# top.net
KiCad netlist of a schematic drawn in Altium Designer
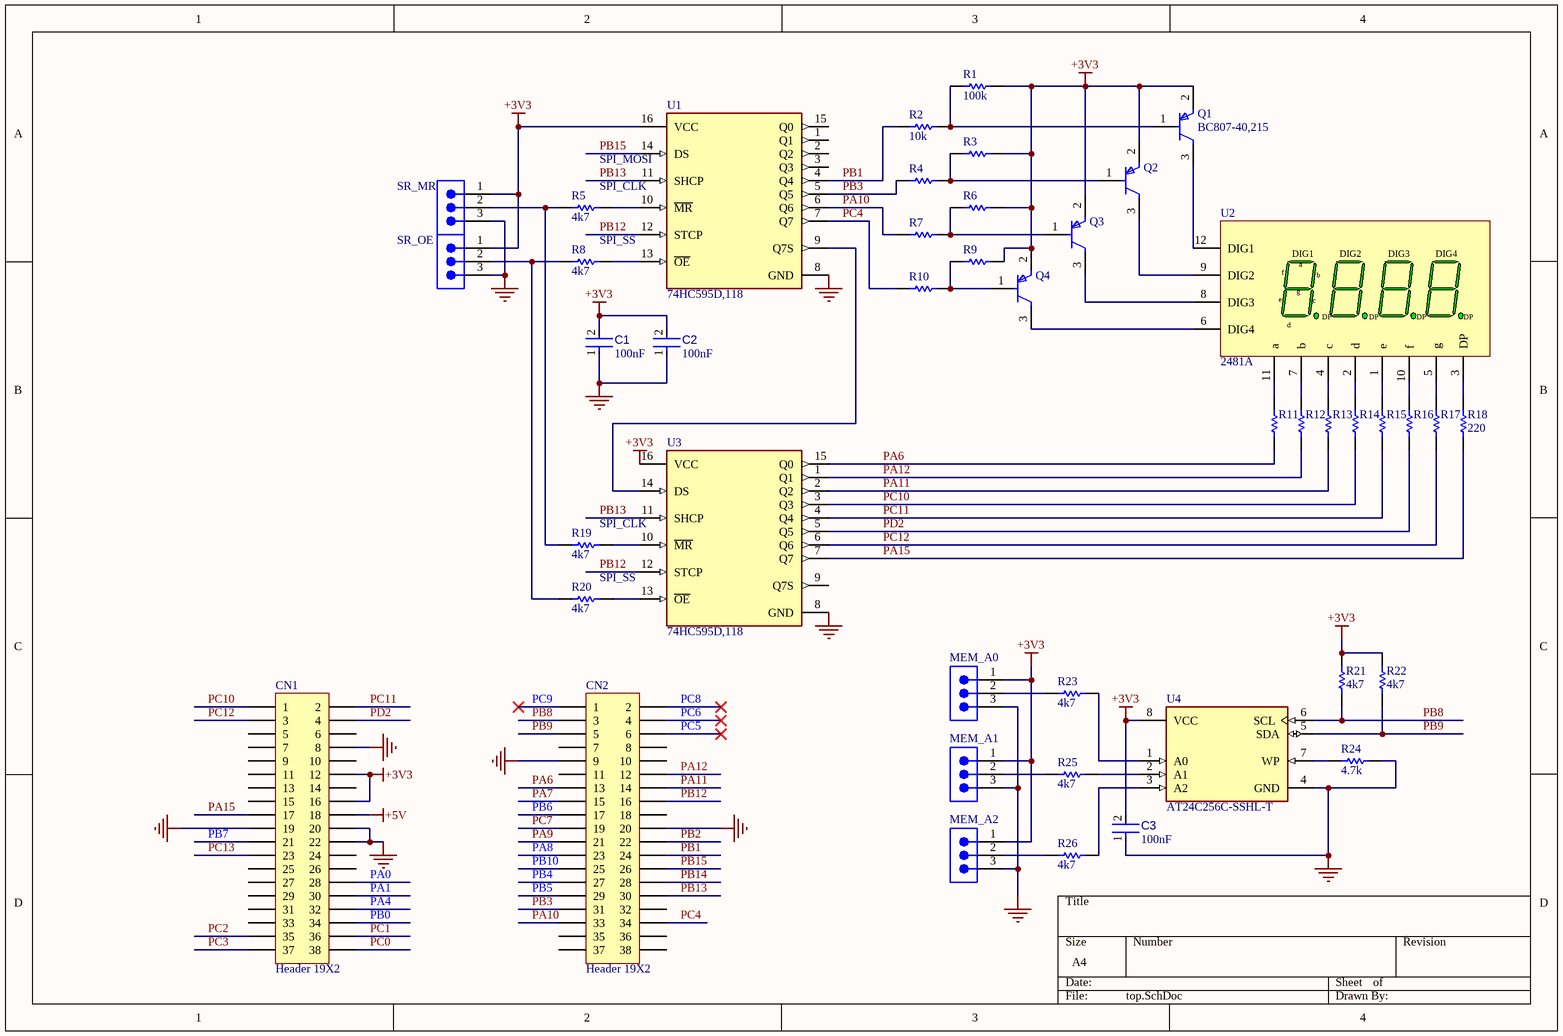
[diagram p0: top.SchDoc]

(export (version "E")
  (design (tool "Eeschema 10.0.6"))
  (components
    (comp (ref "C1")
      (value "UMK107BJ104KAHT")
      (footprint "FP-0603-L_1_6_0_1-W_0_8_0-IPC_A")
      (description "Ceramic Capacitor Automotive 0.1uF ±10% 50V X5R 0603")
      (fields (field (name "TOLERANCE") "10%") (field (name "CAPACITANCE") "100nF"))
      (libsource (lib "Altium Content Vault") (part "02cd4be3c70576c341d710602a673aa"))
    )
    (comp (ref "C2")
      (value "UMK107BJ104KAHT")
      (footprint "FP-0603-L_1_6_0_1-W_0_8_0-IPC_A")
      (description "Ceramic Capacitor Automotive 0.1uF ±10% 50V X5R 0603")
      (fields (field (name "TOLERANCE") "10%") (field (name "CAPACITANCE") "100nF"))
      (libsource (lib "Altium Content Vault") (part "02cd4be3c70576c341d710602a673aa"))
    )
    (comp (ref "C3")
      (value "UMK107BJ104KAHT")
      (footprint "FP-0603-L_1_6_0_1-W_0_8_0-IPC_A")
      (description "Ceramic Capacitor Automotive 0.1uF ±10% 50V X5R 0603")
      (fields (field (name "TOLERANCE") "10%") (field (name "CAPACITANCE") "100nF"))
      (libsource (lib "Altium Content Vault") (part "02cd4be3c70576c341d710602a673aa"))
    )
    (comp (ref "CN1")
      (value "Header 19X2")
      (footprint "2*19P")
      (description "Header, 19-Pin, Dual row")
      (fields (field (name "PUBLISHER") "Altium Limited"))
      (libsource (lib "Nucleo_64_1") (part "Header 19X2"))
    )
    (comp (ref "CN2")
      (value "Header 19X2")
      (footprint "2*19P")
      (description "Header, 19-Pin, Dual row")
      (fields (field (name "PUBLISHER") "Altium Limited"))
      (libsource (lib "Nucleo_64_1") (part "Header 19X2"))
    )
    (comp (ref "MEM_A0")
      (value "TSW-103-07-F-S")
      (footprint "SMTC-TSW-103-07-X-S")
      (description "0.025\" SQ Post Header, Through-hole, Vertical, -55 to 125 degC, 2.54 mm Pitch, 3-Pin, Male, RoHS")
      (fields (field (name "MANUFACTURER") "Samtec"))
      (libsource (lib "Altium Content Vault") (part "SMTC-TSW-103-X-X-S-X"))
    )
    (comp (ref "MEM_A1")
      (value "TSW-103-07-F-S")
      (footprint "SMTC-TSW-103-07-X-S")
      (description "0.025\" SQ Post Header, Through-hole, Vertical, -55 to 125 degC, 2.54 mm Pitch, 3-Pin, Male, RoHS")
      (fields (field (name "MANUFACTURER") "Samtec"))
      (libsource (lib "Altium Content Vault") (part "SMTC-TSW-103-X-X-S-X"))
    )
    (comp (ref "MEM_A2")
      (value "TSW-103-07-F-S")
      (footprint "SMTC-TSW-103-07-X-S")
      (description "0.025\" SQ Post Header, Through-hole, Vertical, -55 to 125 degC, 2.54 mm Pitch, 3-Pin, Male, RoHS")
      (fields (field (name "MANUFACTURER") "Samtec"))
      (libsource (lib "Altium Content Vault") (part "SMTC-TSW-103-X-X-S-X"))
    )
    (comp (ref "Q1")
      (value "BC807-40,215")
      (footprint "FP-SOT23-IPC_A")
      (description "TRANS PNP 45V 500MA TO236AB")
      (libsource (lib "Altium Content Vault") (part "0e8486ed3b47d9c69b8404ba87cf0f7"))
    )
    (comp (ref "Q2")
      (value "BC807-40,215")
      (footprint "FP-SOT23-IPC_A")
      (description "TRANS PNP 45V 500MA TO236AB")
      (libsource (lib "Altium Content Vault") (part "0e8486ed3b47d9c69b8404ba87cf0f7"))
    )
    (comp (ref "Q3")
      (value "BC807-40,215")
      (footprint "FP-SOT23-IPC_A")
      (description "TRANS PNP 45V 500MA TO236AB")
      (libsource (lib "Altium Content Vault") (part "0e8486ed3b47d9c69b8404ba87cf0f7"))
    )
    (comp (ref "Q4")
      (value "BC807-40,215")
      (footprint "FP-SOT23-IPC_A")
      (description "TRANS PNP 45V 500MA TO236AB")
      (libsource (lib "Altium Content Vault") (part "0e8486ed3b47d9c69b8404ba87cf0f7"))
    )
    (comp (ref "R1")
      (value "100k")
      (footprint "RESC1609X55X30ML15T15")
      (description "Chip Resistor, 10 KOhm, +/- 1%, 0.1 W, -55 to 155 degC, 0603 (1608 Metric), RoHS, Tape and Reel")
      (fields (field (name "TOLERANCE") "1%") (field (name "MANUFACTURER") "Panasonic"))
      (libsource (lib "Altium Content Vault") (part "RES-2"))
    )
    (comp (ref "R2")
      (value "10k")
      (footprint "RESC1609X55X30ML15T15")
      (description "Chip Resistor, 10 KOhm, +/- 1%, 0.1 W, -55 to 155 degC, 0603 (1608 Metric), RoHS, Tape and Reel")
      (fields (field (name "TOLERANCE") "1%") (field (name "MANUFACTURER") "Panasonic"))
      (libsource (lib "Altium Content Vault") (part "RES-2"))
    )
    (comp (ref "R3")
      (value "ERJ3EKF1002V")
      (footprint "RESC1609X55X30ML15T15")
      (description "Chip Resistor, 10 KOhm, +/- 1%, 0.1 W, -55 to 155 degC, 0603 (1608 Metric), RoHS, Tape and Reel")
      (fields (field (name "TOLERANCE") "1%") (field (name "MANUFACTURER") "Panasonic"))
      (libsource (lib "Altium Content Vault") (part "RES-2"))
    )
    (comp (ref "R4")
      (value "ERJ3EKF1002V")
      (footprint "RESC1609X55X30ML15T15")
      (description "Chip Resistor, 10 KOhm, +/- 1%, 0.1 W, -55 to 155 degC, 0603 (1608 Metric), RoHS, Tape and Reel")
      (fields (field (name "TOLERANCE") "1%") (field (name "MANUFACTURER") "Panasonic"))
      (libsource (lib "Altium Content Vault") (part "RES-2"))
    )
    (comp (ref "R5")
      (value "4k7")
      (footprint "RESC1608X55X30ML15T15")
      (fields (field (name "TOLERANCE") "5%") (field (name "Comment") "ERJ-3EKF4701V"))
      (libsource (lib "Altium Content Vault") (part "RES-2"))
    )
    (comp (ref "R6")
      (value "ERJ3EKF1002V")
      (footprint "RESC1609X55X30ML15T15")
      (description "Chip Resistor, 10 KOhm, +/- 1%, 0.1 W, -55 to 155 degC, 0603 (1608 Metric), RoHS, Tape and Reel")
      (fields (field (name "TOLERANCE") "1%") (field (name "MANUFACTURER") "Panasonic"))
      (libsource (lib "Altium Content Vault") (part "RES-2"))
    )
    (comp (ref "R7")
      (value "ERJ3EKF1002V")
      (footprint "RESC1609X55X30ML15T15")
      (description "Chip Resistor, 10 KOhm, +/- 1%, 0.1 W, -55 to 155 degC, 0603 (1608 Metric), RoHS, Tape and Reel")
      (fields (field (name "TOLERANCE") "1%") (field (name "MANUFACTURER") "Panasonic"))
      (libsource (lib "Altium Content Vault") (part "RES-2"))
    )
    (comp (ref "R8")
      (value "4k7")
      (footprint "RESC1608X55X30ML15T15")
      (fields (field (name "TOLERANCE") "5%") (field (name "Comment") "ERJ-3EKF4701V"))
      (libsource (lib "Altium Content Vault") (part "RES-2"))
    )
    (comp (ref "R9")
      (value "ERJ3EKF1002V")
      (footprint "RESC1609X55X30ML15T15")
      (description "Chip Resistor, 10 KOhm, +/- 1%, 0.1 W, -55 to 155 degC, 0603 (1608 Metric), RoHS, Tape and Reel")
      (fields (field (name "TOLERANCE") "1%") (field (name "MANUFACTURER") "Panasonic"))
      (libsource (lib "Altium Content Vault") (part "RES-2"))
    )
    (comp (ref "R10")
      (value "ERJ3EKF1002V")
      (footprint "RESC1609X55X30ML15T15")
      (description "Chip Resistor, 10 KOhm, +/- 1%, 0.1 W, -55 to 155 degC, 0603 (1608 Metric), RoHS, Tape and Reel")
      (fields (field (name "TOLERANCE") "1%") (field (name "MANUFACTURER") "Panasonic"))
      (libsource (lib "Altium Content Vault") (part "RES-2"))
    )
    (comp (ref "R11")
      (value "ERJ3EKF1002V")
      (footprint "RESC1609X55X30ML15T15")
      (description "Chip Resistor, 10 KOhm, +/- 1%, 0.1 W, -55 to 155 degC, 0603 (1608 Metric), RoHS, Tape and Reel")
      (fields (field (name "TOLERANCE") "1%") (field (name "MANUFACTURER") "Panasonic"))
      (libsource (lib "Altium Content Vault") (part "RES-2"))
    )
    (comp (ref "R12")
      (value "ERJ3EKF1002V")
      (footprint "RESC1609X55X30ML15T15")
      (description "Chip Resistor, 10 KOhm, +/- 1%, 0.1 W, -55 to 155 degC, 0603 (1608 Metric), RoHS, Tape and Reel")
      (fields (field (name "TOLERANCE") "1%") (field (name "MANUFACTURER") "Panasonic"))
      (libsource (lib "Altium Content Vault") (part "RES-2"))
    )
    (comp (ref "R13")
      (value "ERJ3EKF1002V")
      (footprint "RESC1609X55X30ML15T15")
      (description "Chip Resistor, 10 KOhm, +/- 1%, 0.1 W, -55 to 155 degC, 0603 (1608 Metric), RoHS, Tape and Reel")
      (fields (field (name "TOLERANCE") "1%") (field (name "MANUFACTURER") "Panasonic"))
      (libsource (lib "Altium Content Vault") (part "RES-2"))
    )
    (comp (ref "R14")
      (value "ERJ3EKF1002V")
      (footprint "RESC1609X55X30ML15T15")
      (description "Chip Resistor, 10 KOhm, +/- 1%, 0.1 W, -55 to 155 degC, 0603 (1608 Metric), RoHS, Tape and Reel")
      (fields (field (name "TOLERANCE") "1%") (field (name "MANUFACTURER") "Panasonic"))
      (libsource (lib "Altium Content Vault") (part "RES-2"))
    )
    (comp (ref "R15")
      (value "ERJ3EKF1002V")
      (footprint "RESC1609X55X30ML15T15")
      (description "Chip Resistor, 10 KOhm, +/- 1%, 0.1 W, -55 to 155 degC, 0603 (1608 Metric), RoHS, Tape and Reel")
      (fields (field (name "TOLERANCE") "1%") (field (name "MANUFACTURER") "Panasonic"))
      (libsource (lib "Altium Content Vault") (part "RES-2"))
    )
    (comp (ref "R16")
      (value "ERJ3EKF1002V")
      (footprint "RESC1609X55X30ML15T15")
      (description "Chip Resistor, 10 KOhm, +/- 1%, 0.1 W, -55 to 155 degC, 0603 (1608 Metric), RoHS, Tape and Reel")
      (fields (field (name "TOLERANCE") "1%") (field (name "MANUFACTURER") "Panasonic"))
      (libsource (lib "Altium Content Vault") (part "RES-2"))
    )
    (comp (ref "R17")
      (value "ERJ3EKF1002V")
      (footprint "RESC1609X55X30ML15T15")
      (description "Chip Resistor, 10 KOhm, +/- 1%, 0.1 W, -55 to 155 degC, 0603 (1608 Metric), RoHS, Tape and Reel")
      (fields (field (name "TOLERANCE") "1%") (field (name "MANUFACTURER") "Panasonic"))
      (libsource (lib "Altium Content Vault") (part "RES-2"))
    )
    (comp (ref "R18")
      (value "220")
      (footprint "RESC1609X55X30ML15T15")
      (description "Chip Resistor, 10 KOhm, +/- 1%, 0.1 W, -55 to 155 degC, 0603 (1608 Metric), RoHS, Tape and Reel")
      (fields (field (name "TOLERANCE") "1%") (field (name "MANUFACTURER") "Panasonic"))
      (libsource (lib "Altium Content Vault") (part "RES-2"))
    )
    (comp (ref "R19")
      (value "4k7")
      (footprint "RESC1608X55X30ML15T15")
      (fields (field (name "TOLERANCE") "5%") (field (name "Comment") "ERJ-3EKF4701V"))
      (libsource (lib "Altium Content Vault") (part "RES-2"))
    )
    (comp (ref "R20")
      (value "4k7")
      (footprint "RESC1608X55X30ML15T15")
      (fields (field (name "TOLERANCE") "5%") (field (name "Comment") "ERJ-3EKF4701V"))
      (libsource (lib "Altium Content Vault") (part "RES-2"))
    )
    (comp (ref "R21")
      (value "4k7")
      (footprint "RESC1608X55X30ML15T15")
      (fields (field (name "TOLERANCE") "5%") (field (name "Comment") "ERJ-3EKF4701V"))
      (libsource (lib "Altium Content Vault") (part "RES-2"))
    )
    (comp (ref "R22")
      (value "4k7")
      (footprint "RESC1608X55X30ML15T15")
      (fields (field (name "TOLERANCE") "5%") (field (name "Comment") "ERJ-3EKF4701V"))
      (libsource (lib "Altium Content Vault") (part "RES-2"))
    )
    (comp (ref "R23")
      (value "4k7")
      (footprint "RESC1608X55X30ML15T15")
      (fields (field (name "TOLERANCE") "5%") (field (name "Comment") "ERJ-3EKF4701V"))
      (libsource (lib "Altium Content Vault") (part "RES-2"))
    )
    (comp (ref "R24")
      (value "RC0603FR-074K7L")
      (footprint "RESC1608X55X25ML10T15")
      (description "Chip Resistor, 4.7 KOhm, +/- 1%, 0.1 W, -55 to 155 degC, 0603 (1608 Metric), RoHS, Tape and Reel")
      (fields
        (field (name "MANUFACTURER") "Yageo")
        (field (name "RESISTANCE") "4.7k")
        (field (name "TOLERANCE") "1%")
      )
      (libsource (lib "Altium Content Vault") (part "RES-2"))
    )
    (comp (ref "R25")
      (value "4k7")
      (footprint "RESC1608X55X30ML15T15")
      (fields (field (name "TOLERANCE") "5%") (field (name "Comment") "ERJ-3EKF4701V"))
      (libsource (lib "Altium Content Vault") (part "RES-2"))
    )
    (comp (ref "R26")
      (value "4k7")
      (footprint "RESC1608X55X30ML15T15")
      (fields (field (name "TOLERANCE") "5%") (field (name "Comment") "ERJ-3EKF4701V"))
      (libsource (lib "Altium Content Vault") (part "RES-2"))
    )
    (comp (ref "SR_MR")
      (value "TSW-103-07-F-S")
      (footprint "SMTC-TSW-103-07-X-S")
      (description "0.025\" SQ Post Header, Through-hole, Vertical, -55 to 125 degC, 2.54 mm Pitch, 3-Pin, Male, RoHS")
      (fields (field (name "MANUFACTURER") "Samtec"))
      (libsource (lib "Altium Content Vault") (part "SMTC-TSW-103-X-X-S-X"))
    )
    (comp (ref "SR_OE")
      (value "TSW-103-07-F-S")
      (footprint "SMTC-TSW-103-07-X-S")
      (description "0.025\" SQ Post Header, Through-hole, Vertical, -55 to 125 degC, 2.54 mm Pitch, 3-Pin, Male, RoHS")
      (fields (field (name "MANUFACTURER") "Samtec"))
      (libsource (lib "Altium Content Vault") (part "SMTC-TSW-103-X-X-S-X"))
    )
    (comp (ref "U1")
      (value "74HC595D,118")
      (footprint "FP-SOT109-1-IPC_C")
      (description "IC SHIFT REGISTER 8BIT 16SOIC")
      (libsource (lib "Altium Content Vault") (part "7b153f231cfcc3ac06dee253bd56617"))
    )
    (comp (ref "U2")
      (value "2481A")
      (footprint "2481A")
      (description "7-segment, common-catode")
      (libsource (lib "Components") (part "2481A"))
    )
    (comp (ref "U3")
      (value "74HC595D,118")
      (footprint "FP-SOT109-1-IPC_C")
      (description "IC SHIFT REGISTER 8BIT 16SOIC")
      (libsource (lib "Altium Content Vault") (part "7b153f231cfcc3ac06dee253bd56617"))
    )
    (comp (ref "U4")
      (value "AT24C256C-SSHL-T")
      (footprint "FP-C04-057-SN-MFG")
      (description "IC EEPROM 1KBIT I2C 1MHZ 8SOIC")
      (libsource (lib "Altium Content Vault") (part "d4c6559be2ff01e21c19a0b3011a16c"))
    )
  )
  (nets
    (net (code "1") (name "+3V3") (class "Default")
      (node (ref "C1") (pin "2") (pinfunction "2_2") (pintype "passive"))
      (node (ref "C2") (pin "2") (pinfunction "2_2") (pintype "passive"))
      (node (ref "C3") (pin "2") (pinfunction "2_2") (pintype "passive"))
      (node (ref "CN1") (pin "12") (pinfunction "12_12") (pintype "passive"))
      (node (ref "CN1") (pin "16") (pinfunction "16_16") (pintype "passive"))
      (node (ref "MEM_A0") (pin "1") (pinfunction "1_1") (pintype "passive"))
      (node (ref "MEM_A1") (pin "1") (pinfunction "1_1") (pintype "passive"))
      (node (ref "MEM_A2") (pin "1") (pinfunction "1_1") (pintype "passive"))
      (node (ref "Q1") (pin "2") (pinfunction "E_2") (pintype "passive"))
      (node (ref "Q2") (pin "2") (pinfunction "E_2") (pintype "passive"))
      (node (ref "Q3") (pin "2") (pinfunction "E_2") (pintype "passive"))
      (node (ref "Q4") (pin "2") (pinfunction "E_2") (pintype "passive"))
      (node (ref "R1") (pin "2") (pinfunction "2_2") (pintype "passive"))
      (node (ref "R21") (pin "2") (pinfunction "2_2") (pintype "passive"))
      (node (ref "R22") (pin "2") (pinfunction "2_2") (pintype "passive"))
      (node (ref "R3") (pin "2") (pinfunction "2_2") (pintype "passive"))
      (node (ref "R6") (pin "2") (pinfunction "2_2") (pintype "passive"))
      (node (ref "R9") (pin "2") (pinfunction "2_2") (pintype "passive"))
      (node (ref "SR_MR") (pin "1") (pinfunction "1_1") (pintype "passive"))
      (node (ref "SR_OE") (pin "1") (pinfunction "1_1") (pintype "passive"))
      (node (ref "U1") (pin "16") (pinfunction "VCC_16") (pintype "power_in"))
      (node (ref "U3") (pin "16") (pinfunction "VCC_16") (pintype "power_in"))
      (node (ref "U4") (pin "8") (pinfunction "VCC_8") (pintype "power_in"))
    )
    (net (code "2") (name "+5V") (class "Default")
      (node (ref "CN1") (pin "18") (pinfunction "18_18") (pintype "passive"))
    )
    (net (code "3") (name "/PA0") (class "Default")
      (node (ref "CN1") (pin "28") (pinfunction "28_28") (pintype "passive"))
    )
    (net (code "4") (name "/PA1") (class "Default")
      (node (ref "CN1") (pin "30") (pinfunction "30_30") (pintype "passive"))
    )
    (net (code "5") (name "/PA4") (class "Default")
      (node (ref "CN1") (pin "32") (pinfunction "32_32") (pintype "passive"))
    )
    (net (code "6") (name "/PA6") (class "Default")
      (node (ref "CN2") (pin "13") (pinfunction "13_13") (pintype "passive"))
      (node (ref "R11") (pin "1") (pinfunction "1_1") (pintype "passive"))
      (node (ref "U3") (pin "15") (pinfunction "Q0_15") (pintype "output"))
    )
    (net (code "7") (name "/PA7") (class "Default")
      (node (ref "CN2") (pin "15") (pinfunction "15_15") (pintype "passive"))
    )
    (net (code "8") (name "/PA8") (class "Default")
      (node (ref "CN2") (pin "23") (pinfunction "23_23") (pintype "passive"))
    )
    (net (code "9") (name "/PA9") (class "Default")
      (node (ref "CN2") (pin "21") (pinfunction "21_21") (pintype "passive"))
    )
    (net (code "10") (name "/PA10") (class "Default")
      (node (ref "CN2") (pin "33") (pinfunction "33_33") (pintype "passive"))
      (node (ref "R7") (pin "1") (pinfunction "1_1") (pintype "passive"))
      (node (ref "U1") (pin "6") (pinfunction "Q6_6") (pintype "output"))
    )
    (net (code "11") (name "/PA11") (class "Default")
      (node (ref "CN2") (pin "14") (pinfunction "14_14") (pintype "passive"))
      (node (ref "R13") (pin "1") (pinfunction "1_1") (pintype "passive"))
      (node (ref "U3") (pin "2") (pinfunction "Q2_2") (pintype "output"))
    )
    (net (code "12") (name "/PA12") (class "Default")
      (node (ref "CN2") (pin "12") (pinfunction "12_12") (pintype "passive"))
      (node (ref "R12") (pin "1") (pinfunction "1_1") (pintype "passive"))
      (node (ref "U3") (pin "1") (pinfunction "Q1_1") (pintype "output"))
    )
    (net (code "13") (name "/PA15") (class "Default")
      (node (ref "CN1") (pin "17") (pinfunction "17_17") (pintype "passive"))
      (node (ref "R18") (pin "1") (pinfunction "1_1") (pintype "passive"))
      (node (ref "U3") (pin "7") (pinfunction "Q7_7") (pintype "output"))
    )
    (net (code "14") (name "/PB0") (class "Default")
      (node (ref "CN1") (pin "34") (pinfunction "34_34") (pintype "passive"))
    )
    (net (code "15") (name "/PB1") (class "Default")
      (node (ref "CN2") (pin "24") (pinfunction "24_24") (pintype "passive"))
      (node (ref "R2") (pin "1") (pinfunction "1_1") (pintype "passive"))
      (node (ref "U1") (pin "4") (pinfunction "Q4_4") (pintype "output"))
    )
    (net (code "16") (name "/PB2") (class "Default")
      (node (ref "CN2") (pin "22") (pinfunction "22_22") (pintype "passive"))
    )
    (net (code "17") (name "/PB3") (class "Default")
      (node (ref "CN2") (pin "31") (pinfunction "31_31") (pintype "passive"))
      (node (ref "R4") (pin "1") (pinfunction "1_1") (pintype "passive"))
      (node (ref "U1") (pin "5") (pinfunction "Q5_5") (pintype "output"))
    )
    (net (code "18") (name "/PB4") (class "Default")
      (node (ref "CN2") (pin "27") (pinfunction "27_27") (pintype "passive"))
    )
    (net (code "19") (name "/PB5") (class "Default")
      (node (ref "CN2") (pin "29") (pinfunction "29_29") (pintype "passive"))
    )
    (net (code "20") (name "/PB6") (class "Default")
      (node (ref "CN2") (pin "17") (pinfunction "17_17") (pintype "passive"))
    )
    (net (code "21") (name "/PB7") (class "Default")
      (node (ref "CN1") (pin "21") (pinfunction "21_21") (pintype "passive"))
    )
    (net (code "22") (name "/PB8") (class "Default")
      (node (ref "CN2") (pin "3") (pinfunction "3_3") (pintype "passive"))
      (node (ref "R21") (pin "1") (pinfunction "1_1") (pintype "passive"))
      (node (ref "U4") (pin "6") (pinfunction "SCL_6") (pintype "input"))
    )
    (net (code "23") (name "/PB9") (class "Default")
      (node (ref "CN2") (pin "5") (pinfunction "5_5") (pintype "passive"))
      (node (ref "R22") (pin "1") (pinfunction "1_1") (pintype "passive"))
      (node (ref "U4") (pin "5") (pinfunction "SDA_5") (pintype "bidirectional"))
    )
    (net (code "24") (name "/PB10") (class "Default")
      (node (ref "CN2") (pin "25") (pinfunction "25_25") (pintype "passive"))
    )
    (net (code "25") (name "/PB12") (class "Default")
      (node (ref "CN2") (pin "16") (pinfunction "16_16") (pintype "passive"))
      (node (ref "U1") (pin "12") (pinfunction "STCP_12") (pintype "input"))
      (node (ref "U3") (pin "12") (pinfunction "STCP_12") (pintype "input"))
    )
    (net (code "26") (name "/PB13") (class "Default")
      (node (ref "CN2") (pin "30") (pinfunction "30_30") (pintype "passive"))
      (node (ref "U1") (pin "11") (pinfunction "SHCP_11") (pintype "input"))
      (node (ref "U3") (pin "11") (pinfunction "SHCP_11") (pintype "input"))
    )
    (net (code "27") (name "/PB14") (class "Default")
      (node (ref "CN2") (pin "28") (pinfunction "28_28") (pintype "passive"))
    )
    (net (code "28") (name "/PB15") (class "Default")
      (node (ref "CN2") (pin "26") (pinfunction "26_26") (pintype "passive"))
      (node (ref "U1") (pin "14") (pinfunction "DS_14") (pintype "input"))
    )
    (net (code "29") (name "/PC0") (class "Default")
      (node (ref "CN1") (pin "38") (pinfunction "38_38") (pintype "passive"))
    )
    (net (code "30") (name "/PC1") (class "Default")
      (node (ref "CN1") (pin "36") (pinfunction "36_36") (pintype "passive"))
    )
    (net (code "31") (name "/PC2") (class "Default")
      (node (ref "CN1") (pin "35") (pinfunction "35_35") (pintype "passive"))
    )
    (net (code "32") (name "/PC3") (class "Default")
      (node (ref "CN1") (pin "37") (pinfunction "37_37") (pintype "passive"))
    )
    (net (code "33") (name "/PC4") (class "Default")
      (node (ref "CN2") (pin "34") (pinfunction "34_34") (pintype "passive"))
      (node (ref "R10") (pin "1") (pinfunction "1_1") (pintype "passive"))
      (node (ref "U1") (pin "7") (pinfunction "Q7_7") (pintype "output"))
    )
    (net (code "34") (name "/PC5") (class "Default")
      (node (ref "CN2") (pin "6") (pinfunction "6_6") (pintype "passive+no_connect"))
    )
    (net (code "35") (name "/PC6") (class "Default")
      (node (ref "CN2") (pin "4") (pinfunction "4_4") (pintype "passive+no_connect"))
    )
    (net (code "36") (name "/PC7") (class "Default")
      (node (ref "CN2") (pin "19") (pinfunction "19_19") (pintype "passive"))
    )
    (net (code "37") (name "/PC8") (class "Default")
      (node (ref "CN2") (pin "2") (pinfunction "2_2") (pintype "passive+no_connect"))
    )
    (net (code "38") (name "/PC9") (class "Default")
      (node (ref "CN2") (pin "1") (pinfunction "1_1") (pintype "passive+no_connect"))
    )
    (net (code "39") (name "/PC10") (class "Default")
      (node (ref "CN1") (pin "1") (pinfunction "1_1") (pintype "passive"))
      (node (ref "R14") (pin "1") (pinfunction "1_1") (pintype "passive"))
      (node (ref "U3") (pin "3") (pinfunction "Q3_3") (pintype "output"))
    )
    (net (code "40") (name "/PC11") (class "Default")
      (node (ref "CN1") (pin "2") (pinfunction "2_2") (pintype "passive"))
      (node (ref "R15") (pin "1") (pinfunction "1_1") (pintype "passive"))
      (node (ref "U3") (pin "4") (pinfunction "Q4_4") (pintype "output"))
    )
    (net (code "41") (name "/PC12") (class "Default")
      (node (ref "CN1") (pin "3") (pinfunction "3_3") (pintype "passive"))
      (node (ref "R17") (pin "1") (pinfunction "1_1") (pintype "passive"))
      (node (ref "U3") (pin "6") (pinfunction "Q6_6") (pintype "output"))
    )
    (net (code "42") (name "/PC13") (class "Default")
      (node (ref "CN1") (pin "23") (pinfunction "23_23") (pintype "passive"))
    )
    (net (code "43") (name "/PD2") (class "Default")
      (node (ref "CN1") (pin "4") (pinfunction "4_4") (pintype "passive"))
      (node (ref "R16") (pin "1") (pinfunction "1_1") (pintype "passive"))
      (node (ref "U3") (pin "5") (pinfunction "Q5_5") (pintype "output"))
    )
    (net (code "44") (name "GND") (class "Default")
      (node (ref "C1") (pin "1") (pinfunction "1_1") (pintype "passive"))
      (node (ref "C2") (pin "1") (pinfunction "1_1") (pintype "passive"))
      (node (ref "C3") (pin "1") (pinfunction "1_1") (pintype "passive"))
      (node (ref "CN1") (pin "19") (pinfunction "19_19") (pintype "passive"))
      (node (ref "CN1") (pin "20") (pinfunction "20_20") (pintype "passive"))
      (node (ref "CN1") (pin "22") (pinfunction "22_22") (pintype "passive"))
      (node (ref "CN1") (pin "8") (pinfunction "8_8") (pintype "passive"))
      (node (ref "CN2") (pin "20") (pinfunction "20_20") (pintype "passive"))
      (node (ref "CN2") (pin "9") (pinfunction "9_9") (pintype "passive"))
      (node (ref "MEM_A0") (pin "3") (pinfunction "3_3") (pintype "passive"))
      (node (ref "MEM_A1") (pin "3") (pinfunction "3_3") (pintype "passive"))
      (node (ref "MEM_A2") (pin "3") (pinfunction "3_3") (pintype "passive"))
      (node (ref "R24") (pin "2") (pinfunction "2_2") (pintype "passive"))
      (node (ref "SR_MR") (pin "3") (pinfunction "3_3") (pintype "passive"))
      (node (ref "SR_OE") (pin "3") (pinfunction "3_3") (pintype "passive"))
      (node (ref "U1") (pin "8") (pinfunction "GND_8") (pintype "power_in"))
      (node (ref "U3") (pin "8") (pinfunction "GND_8") (pintype "power_in"))
      (node (ref "U4") (pin "4") (pinfunction "GND_4") (pintype "power_in"))
    )
    (net (code "45") (name "Net-(MEM_A0-Pad2)") (class "Default")
      (node (ref "MEM_A0") (pin "2") (pinfunction "2_2") (pintype "passive"))
      (node (ref "R23") (pin "2") (pinfunction "2_2") (pintype "passive"))
    )
    (net (code "46") (name "Net-(MEM_A1-Pad2)") (class "Default")
      (node (ref "MEM_A1") (pin "2") (pinfunction "2_2") (pintype "passive"))
      (node (ref "R25") (pin "2") (pinfunction "2_2") (pintype "passive"))
    )
    (net (code "47") (name "Net-(MEM_A2-Pad2)") (class "Default")
      (node (ref "MEM_A2") (pin "2") (pinfunction "2_2") (pintype "passive"))
      (node (ref "R26") (pin "2") (pinfunction "2_2") (pintype "passive"))
    )
    (net (code "48") (name "Net-(Q1-B)") (class "Default")
      (node (ref "Q1") (pin "1") (pinfunction "B_1") (pintype "passive"))
      (node (ref "R1") (pin "1") (pinfunction "1_1") (pintype "passive"))
      (node (ref "R2") (pin "2") (pinfunction "2_2") (pintype "passive"))
    )
    (net (code "49") (name "Net-(Q1-C)") (class "Default")
      (node (ref "Q1") (pin "3") (pinfunction "C_3") (pintype "passive"))
      (node (ref "U2") (pin "12") (pinfunction "DIG1_12") (pintype "passive"))
    )
    (net (code "50") (name "Net-(Q2-B)") (class "Default")
      (node (ref "Q2") (pin "1") (pinfunction "B_1") (pintype "passive"))
      (node (ref "R3") (pin "1") (pinfunction "1_1") (pintype "passive"))
      (node (ref "R4") (pin "2") (pinfunction "2_2") (pintype "passive"))
    )
    (net (code "51") (name "Net-(Q2-C)") (class "Default")
      (node (ref "Q2") (pin "3") (pinfunction "C_3") (pintype "passive"))
      (node (ref "U2") (pin "9") (pinfunction "DIG2_9") (pintype "passive"))
    )
    (net (code "52") (name "Net-(Q3-B)") (class "Default")
      (node (ref "Q3") (pin "1") (pinfunction "B_1") (pintype "passive"))
      (node (ref "R6") (pin "1") (pinfunction "1_1") (pintype "passive"))
      (node (ref "R7") (pin "2") (pinfunction "2_2") (pintype "passive"))
    )
    (net (code "53") (name "Net-(Q3-C)") (class "Default")
      (node (ref "Q3") (pin "3") (pinfunction "C_3") (pintype "passive"))
      (node (ref "U2") (pin "8") (pinfunction "DIG3_8") (pintype "passive"))
    )
    (net (code "54") (name "Net-(Q4-B)") (class "Default")
      (node (ref "Q4") (pin "1") (pinfunction "B_1") (pintype "passive"))
      (node (ref "R10") (pin "2") (pinfunction "2_2") (pintype "passive"))
      (node (ref "R9") (pin "1") (pinfunction "1_1") (pintype "passive"))
    )
    (net (code "55") (name "Net-(Q4-C)") (class "Default")
      (node (ref "Q4") (pin "3") (pinfunction "C_3") (pintype "passive"))
      (node (ref "U2") (pin "6") (pinfunction "DIG4_6") (pintype "passive"))
    )
    (net (code "56") (name "Net-(R19-Pad2)") (class "Default")
      (node (ref "R19") (pin "2") (pinfunction "2_2") (pintype "passive"))
      (node (ref "R5") (pin "2") (pinfunction "2_2") (pintype "passive"))
      (node (ref "SR_MR") (pin "2") (pinfunction "2_2") (pintype "passive"))
    )
    (net (code "57") (name "Net-(R20-Pad2)") (class "Default")
      (node (ref "R20") (pin "2") (pinfunction "2_2") (pintype "passive"))
      (node (ref "R8") (pin "2") (pinfunction "2_2") (pintype "passive"))
      (node (ref "SR_OE") (pin "2") (pinfunction "2_2") (pintype "passive"))
    )
    (net (code "58") (name "Net-(U1-Q7S)") (class "Default")
      (node (ref "U1") (pin "9") (pinfunction "Q7S_9") (pintype "output"))
      (node (ref "U3") (pin "14") (pinfunction "DS_14") (pintype "input"))
    )
    (net (code "59") (name "Net-(U1-~{MR})") (class "Default")
      (node (ref "R5") (pin "1") (pinfunction "1_1") (pintype "passive"))
      (node (ref "U1") (pin "10") (pinfunction "~{MR}_10") (pintype "input"))
    )
    (net (code "60") (name "Net-(U1-~{OE})") (class "Default")
      (node (ref "R8") (pin "1") (pinfunction "1_1") (pintype "passive"))
      (node (ref "U1") (pin "13") (pinfunction "~{OE}_13") (pintype "input"))
    )
    (net (code "61") (name "Net-(U2-DP)") (class "Default")
      (node (ref "R18") (pin "2") (pinfunction "2_2") (pintype "passive"))
      (node (ref "U2") (pin "3") (pinfunction "DP_3") (pintype "passive"))
    )
    (net (code "62") (name "Net-(U2-a)") (class "Default")
      (node (ref "R11") (pin "2") (pinfunction "2_2") (pintype "passive"))
      (node (ref "U2") (pin "11") (pinfunction "a_11") (pintype "passive"))
    )
    (net (code "63") (name "Net-(U2-b)") (class "Default")
      (node (ref "R12") (pin "2") (pinfunction "2_2") (pintype "passive"))
      (node (ref "U2") (pin "7") (pinfunction "b_7") (pintype "passive"))
    )
    (net (code "64") (name "Net-(U2-c)") (class "Default")
      (node (ref "R13") (pin "2") (pinfunction "2_2") (pintype "passive"))
      (node (ref "U2") (pin "4") (pinfunction "c_4") (pintype "passive"))
    )
    (net (code "65") (name "Net-(U2-d)") (class "Default")
      (node (ref "R14") (pin "2") (pinfunction "2_2") (pintype "passive"))
      (node (ref "U2") (pin "2") (pinfunction "d_2") (pintype "passive"))
    )
    (net (code "66") (name "Net-(U2-e)") (class "Default")
      (node (ref "R15") (pin "2") (pinfunction "2_2") (pintype "passive"))
      (node (ref "U2") (pin "1") (pinfunction "e_1") (pintype "passive"))
    )
    (net (code "67") (name "Net-(U2-f)") (class "Default")
      (node (ref "R16") (pin "2") (pinfunction "2_2") (pintype "passive"))
      (node (ref "U2") (pin "10") (pinfunction "f_10") (pintype "passive"))
    )
    (net (code "68") (name "Net-(U2-g)") (class "Default")
      (node (ref "R17") (pin "2") (pinfunction "2_2") (pintype "passive"))
      (node (ref "U2") (pin "5") (pinfunction "g_5") (pintype "passive"))
    )
    (net (code "69") (name "Net-(U3-~{MR})") (class "Default")
      (node (ref "R19") (pin "1") (pinfunction "1_1") (pintype "passive"))
      (node (ref "U3") (pin "10") (pinfunction "~{MR}_10") (pintype "input"))
    )
    (net (code "70") (name "Net-(U3-~{OE})") (class "Default")
      (node (ref "R20") (pin "1") (pinfunction "1_1") (pintype "passive"))
      (node (ref "U3") (pin "13") (pinfunction "~{OE}_13") (pintype "input"))
    )
    (net (code "71") (name "Net-(U4-A0)") (class "Default")
      (node (ref "R23") (pin "1") (pinfunction "1_1") (pintype "passive"))
      (node (ref "U4") (pin "1") (pinfunction "A0_1") (pintype "input"))
    )
    (net (code "72") (name "Net-(U4-A1)") (class "Default")
      (node (ref "R25") (pin "1") (pinfunction "1_1") (pintype "passive"))
      (node (ref "U4") (pin "2") (pinfunction "A1_2") (pintype "input"))
    )
    (net (code "73") (name "Net-(U4-A2)") (class "Default")
      (node (ref "R26") (pin "1") (pinfunction "1_1") (pintype "passive"))
      (node (ref "U4") (pin "3") (pinfunction "A2_3") (pintype "input"))
    )
    (net (code "74") (name "Net-(U4-WP)") (class "Default")
      (node (ref "R24") (pin "1") (pinfunction "1_1") (pintype "passive"))
      (node (ref "U4") (pin "7") (pinfunction "WP_7") (pintype "input"))
    )
    (net (code "75") (name "unconnected-(CN1-Pad5)") (class "Default")
      (node (ref "CN1") (pin "5") (pinfunction "5_5") (pintype "passive"))
    )
    (net (code "76") (name "unconnected-(CN1-Pad6)") (class "Default")
      (node (ref "CN1") (pin "6") (pinfunction "6_6") (pintype "passive"))
    )
    (net (code "77") (name "unconnected-(CN1-Pad7)") (class "Default")
      (node (ref "CN1") (pin "7") (pinfunction "7_7") (pintype "passive"))
    )
    (net (code "78") (name "unconnected-(CN1-Pad9)") (class "Default")
      (node (ref "CN1") (pin "9") (pinfunction "9_9") (pintype "passive"))
    )
    (net (code "79") (name "unconnected-(CN1-Pad10)") (class "Default")
      (node (ref "CN1") (pin "10") (pinfunction "10_10") (pintype "passive"))
    )
    (net (code "80") (name "unconnected-(CN1-Pad11)") (class "Default")
      (node (ref "CN1") (pin "11") (pinfunction "11_11") (pintype "passive"))
    )
    (net (code "81") (name "unconnected-(CN1-Pad13)") (class "Default")
      (node (ref "CN1") (pin "13") (pinfunction "13_13") (pintype "passive"))
    )
    (net (code "82") (name "unconnected-(CN1-Pad14)") (class "Default")
      (node (ref "CN1") (pin "14") (pinfunction "14_14") (pintype "passive"))
    )
    (net (code "83") (name "unconnected-(CN1-Pad15)") (class "Default")
      (node (ref "CN1") (pin "15") (pinfunction "15_15") (pintype "passive"))
    )
    (net (code "84") (name "unconnected-(CN1-Pad24)") (class "Default")
      (node (ref "CN1") (pin "24") (pinfunction "24_24") (pintype "passive"))
    )
    (net (code "85") (name "unconnected-(CN1-Pad25)") (class "Default")
      (node (ref "CN1") (pin "25") (pinfunction "25_25") (pintype "passive"))
    )
    (net (code "86") (name "unconnected-(CN1-Pad26)") (class "Default")
      (node (ref "CN1") (pin "26") (pinfunction "26_26") (pintype "passive"))
    )
    (net (code "87") (name "unconnected-(CN1-Pad27)") (class "Default")
      (node (ref "CN1") (pin "27") (pinfunction "27_27") (pintype "passive"))
    )
    (net (code "88") (name "unconnected-(CN1-Pad29)") (class "Default")
      (node (ref "CN1") (pin "29") (pinfunction "29_29") (pintype "passive"))
    )
    (net (code "89") (name "unconnected-(CN1-Pad31)") (class "Default")
      (node (ref "CN1") (pin "31") (pinfunction "31_31") (pintype "passive"))
    )
    (net (code "90") (name "unconnected-(CN1-Pad33)") (class "Default")
      (node (ref "CN1") (pin "33") (pinfunction "33_33") (pintype "passive"))
    )
    (net (code "91") (name "unconnected-(CN2-Pad7)") (class "Default")
      (node (ref "CN2") (pin "7") (pinfunction "7_7") (pintype "passive"))
    )
    (net (code "92") (name "unconnected-(CN2-Pad8)") (class "Default")
      (node (ref "CN2") (pin "8") (pinfunction "8_8") (pintype "passive"))
    )
    (net (code "93") (name "unconnected-(CN2-Pad10)") (class "Default")
      (node (ref "CN2") (pin "10") (pinfunction "10_10") (pintype "passive"))
    )
    (net (code "94") (name "unconnected-(CN2-Pad11)") (class "Default")
      (node (ref "CN2") (pin "11") (pinfunction "11_11") (pintype "passive"))
    )
    (net (code "95") (name "unconnected-(CN2-Pad18)") (class "Default")
      (node (ref "CN2") (pin "18") (pinfunction "18_18") (pintype "passive"))
    )
    (net (code "96") (name "unconnected-(CN2-Pad32)") (class "Default")
      (node (ref "CN2") (pin "32") (pinfunction "32_32") (pintype "passive"))
    )
    (net (code "97") (name "unconnected-(CN2-Pad35)") (class "Default")
      (node (ref "CN2") (pin "35") (pinfunction "35_35") (pintype "passive"))
    )
    (net (code "98") (name "unconnected-(CN2-Pad36)") (class "Default")
      (node (ref "CN2") (pin "36") (pinfunction "36_36") (pintype "passive"))
    )
    (net (code "99") (name "unconnected-(CN2-Pad37)") (class "Default")
      (node (ref "CN2") (pin "37") (pinfunction "37_37") (pintype "passive"))
    )
    (net (code "100") (name "unconnected-(CN2-Pad38)") (class "Default")
      (node (ref "CN2") (pin "38") (pinfunction "38_38") (pintype "passive"))
    )
    (net (code "101") (name "unconnected-(U1-Q0-Pad15)") (class "Default")
      (node (ref "U1") (pin "15") (pinfunction "Q0_15") (pintype "output"))
    )
    (net (code "102") (name "unconnected-(U1-Q1-Pad1)") (class "Default")
      (node (ref "U1") (pin "1") (pinfunction "Q1_1") (pintype "output"))
    )
    (net (code "103") (name "unconnected-(U1-Q2-Pad2)") (class "Default")
      (node (ref "U1") (pin "2") (pinfunction "Q2_2") (pintype "output"))
    )
    (net (code "104") (name "unconnected-(U1-Q3-Pad3)") (class "Default")
      (node (ref "U1") (pin "3") (pinfunction "Q3_3") (pintype "output"))
    )
    (net (code "105") (name "unconnected-(U3-Q7S-Pad9)") (class "Default")
      (node (ref "U3") (pin "9") (pinfunction "Q7S_9") (pintype "output"))
    )
  )
)
